# magspoof-schematic-dip.net
KiCad netlist of a schematic drawn in EAGLE
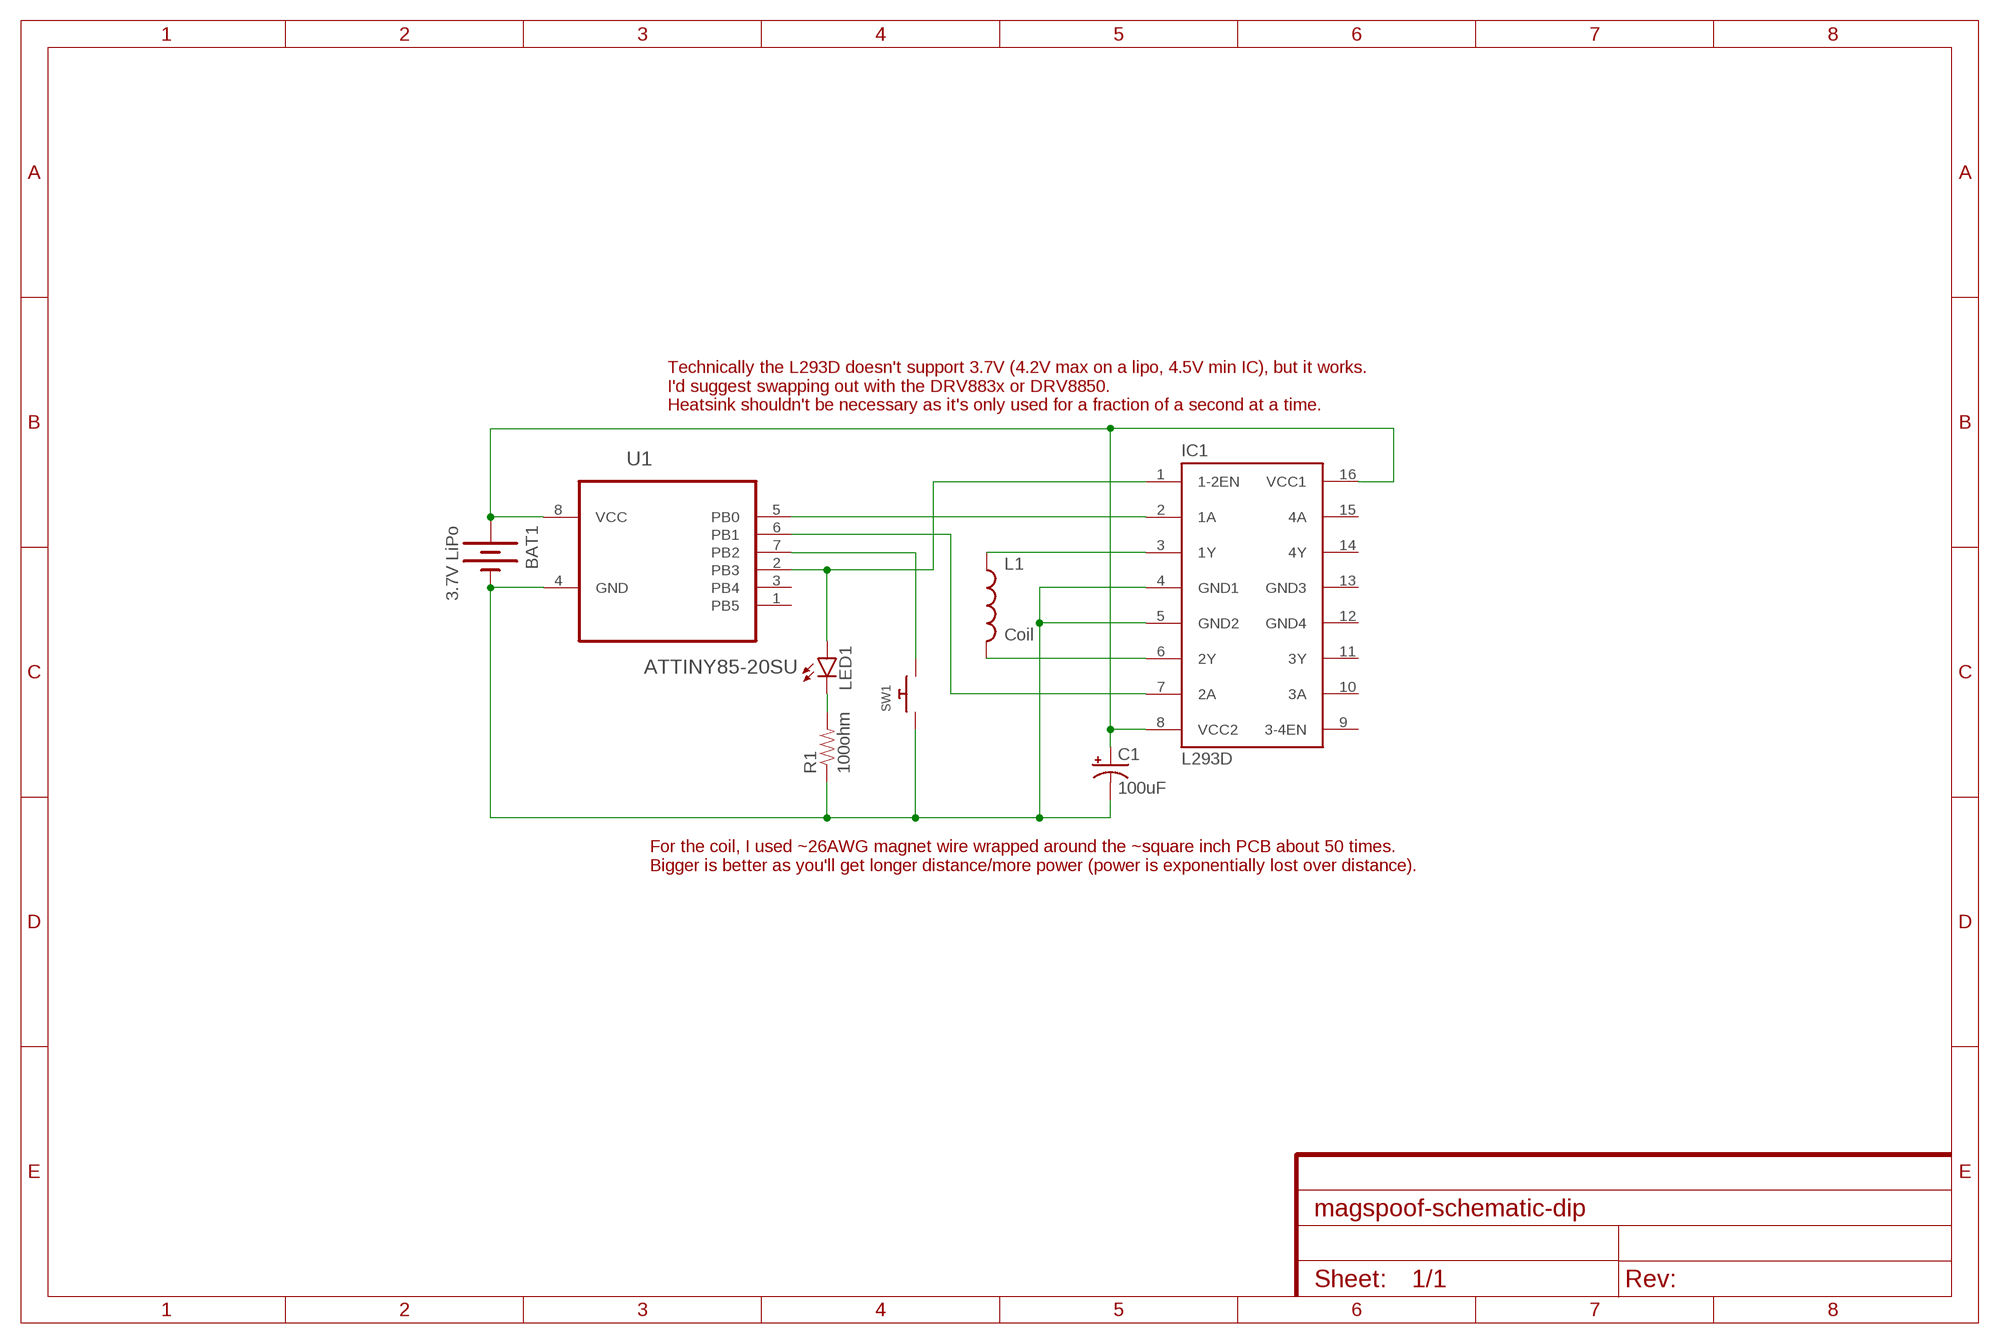
[diagram p0: schematic, sheet 1]

(export (version "E")
  (design (tool "Eeschema 10.0.6"))
  (components
    (comp (ref "BAT1")
      (value "3.7V LiPo")
      (footprint "eagle-import:LIPO-110-TABS")
      (libsource (lib "eagle-import") (part "BATTERYLIPO-TABS"))
    )
    (comp (ref "C1")
      (value "100uF")
      (footprint "eagle-import:CPOL-RADIAL-100UF-25V")
      (libsource (lib "eagle-import") (part "CAP_POLPTH1"))
    )
    (comp (ref "IC1")
      (value "L293D")
      (footprint "eagle-import:DIL16")
      (libsource (lib "eagle-import") (part "L293D"))
    )
    (comp (ref "L1")
      (value "Coil")
      (footprint "eagle-import:AXIAL-0.6")
      (libsource (lib "eagle-import") (part "INDUCTORAXIAL-0.6"))
    )
    (comp (ref "LED1")
      (value "LED-3MM-NO_SILK")
      (footprint "eagle-import:LED3MM-NS")
      (libsource (lib "eagle-import") (part "LED-3MM-NO_SILK"))
    )
    (comp (ref "R1")
      (value "100ohm")
      (footprint "eagle-import:AXIAL-0.3")
      (libsource (lib "eagle-import") (part "RESISTORAXIAL-0.3"))
    )
    (comp (ref "SW1")
      (value "SWITCH_PUSHBUTTONEVQ-PE")
      (footprint "eagle-import:TACT_PANA-EVQ")
      (libsource (lib "eagle-import") (part "SWITCH_PUSHBUTTONEVQ-PE"))
    )
    (comp (ref "U1")
      (value "ATTINY85-20SU")
      (footprint "eagle-import:SOIC127P798X216-8N")
      (libsource (lib "eagle-import") (part "ATTINY85-20SU"))
    )
  )
  (nets
    (net (code "1") (name "/GND3") (class "Default")
      (node (ref "IC1") (pin "13") (pinfunction "GND3_13") (pintype "power_in"))
    )
    (net (code "2") (name "/GND4") (class "Default")
      (node (ref "IC1") (pin "12") (pinfunction "GND4_12") (pintype "power_in"))
    )
    (net (code "3") (name "Net-(C1-+)") (class "Default")
      (node (ref "BAT1") (pin "+") (pinfunction "+_+") (pintype "power_in"))
      (node (ref "C1") (pin "1") (pinfunction "+_1") (pintype "passive"))
      (node (ref "IC1") (pin "16") (pinfunction "VCC1_16") (pintype "power_in"))
      (node (ref "IC1") (pin "8") (pinfunction "VCC2_8") (pintype "power_in"))
      (node (ref "U1") (pin "8") (pinfunction "VCC_8") (pintype "power_in"))
    )
    (net (code "4") (name "Net-(C1--)") (class "Default")
      (node (ref "BAT1") (pin "-") (pinfunction "-_-") (pintype "power_in"))
      (node (ref "C1") (pin "2") (pinfunction "-_2") (pintype "passive"))
      (node (ref "IC1") (pin "4") (pinfunction "GND1_4") (pintype "power_in"))
      (node (ref "IC1") (pin "5") (pinfunction "GND2_5") (pintype "power_in"))
      (node (ref "R1") (pin "P$1") (pinfunction "1_P$1") (pintype "passive"))
      (node (ref "SW1") (pin "P$1") (pinfunction "P$1_P$1") (pintype "passive"))
      (node (ref "U1") (pin "4") (pinfunction "GND_4") (pintype "passive"))
    )
    (net (code "5") (name "Net-(IC1-1-2EN)") (class "Default")
      (node (ref "IC1") (pin "1") (pinfunction "1-2EN_1") (pintype "input"))
      (node (ref "LED1") (pin "A") (pinfunction "A_A") (pintype "passive"))
      (node (ref "U1") (pin "2") (pinfunction "PB3_2") (pintype "bidirectional"))
    )
    (net (code "6") (name "Net-(IC1-1A)") (class "Default")
      (node (ref "IC1") (pin "2") (pinfunction "1A_2") (pintype "input"))
      (node (ref "U1") (pin "5") (pinfunction "PB0_5") (pintype "bidirectional"))
    )
    (net (code "7") (name "Net-(IC1-1Y)") (class "Default")
      (node (ref "IC1") (pin "3") (pinfunction "1Y_3") (pintype "output"))
      (node (ref "L1") (pin "P$1") (pinfunction "1_P$1") (pintype "passive"))
    )
    (net (code "8") (name "Net-(IC1-2A)") (class "Default")
      (node (ref "IC1") (pin "7") (pinfunction "2A_7") (pintype "input"))
      (node (ref "U1") (pin "6") (pinfunction "PB1_6") (pintype "bidirectional"))
    )
    (net (code "9") (name "Net-(IC1-2Y)") (class "Default")
      (node (ref "IC1") (pin "6") (pinfunction "2Y_6") (pintype "output"))
      (node (ref "L1") (pin "P$2") (pinfunction "2_P$2") (pintype "passive"))
    )
    (net (code "10") (name "Net-(LED1-C)") (class "Default")
      (node (ref "LED1") (pin "K") (pinfunction "C_K") (pintype "passive"))
      (node (ref "R1") (pin "P$2") (pinfunction "2_P$2") (pintype "passive"))
    )
    (net (code "11") (name "Net-(U1-PB2)") (class "Default")
      (node (ref "SW1") (pin "P$2") (pinfunction "P$2_P$2") (pintype "passive"))
      (node (ref "U1") (pin "7") (pinfunction "PB2_7") (pintype "bidirectional"))
    )
    (net (code "12") (name "unconnected-(IC1-3-4EN-Pad9)") (class "Default")
      (node (ref "IC1") (pin "9") (pinfunction "3-4EN_9") (pintype "input"))
    )
    (net (code "13") (name "unconnected-(IC1-3A-Pad10)") (class "Default")
      (node (ref "IC1") (pin "10") (pinfunction "3A_10") (pintype "input"))
    )
    (net (code "14") (name "unconnected-(IC1-3Y-Pad11)") (class "Default")
      (node (ref "IC1") (pin "11") (pinfunction "3Y_11") (pintype "output"))
    )
    (net (code "15") (name "unconnected-(IC1-4A-Pad15)") (class "Default")
      (node (ref "IC1") (pin "15") (pinfunction "4A_15") (pintype "input"))
    )
    (net (code "16") (name "unconnected-(IC1-4Y-Pad14)") (class "Default")
      (node (ref "IC1") (pin "14") (pinfunction "4Y_14") (pintype "output"))
    )
    (net (code "17") (name "unconnected-(U1-PB4-Pad3)") (class "Default")
      (node (ref "U1") (pin "3") (pinfunction "PB4_3") (pintype "bidirectional"))
    )
    (net (code "18") (name "unconnected-(U1-PB5-Pad1)") (class "Default")
      (node (ref "U1") (pin "1") (pinfunction "PB5_1") (pintype "bidirectional"))
    )
  )
)
